# FIDO2AUTH_0022.net
KiCad netlist of a schematic drawn in EAGLE
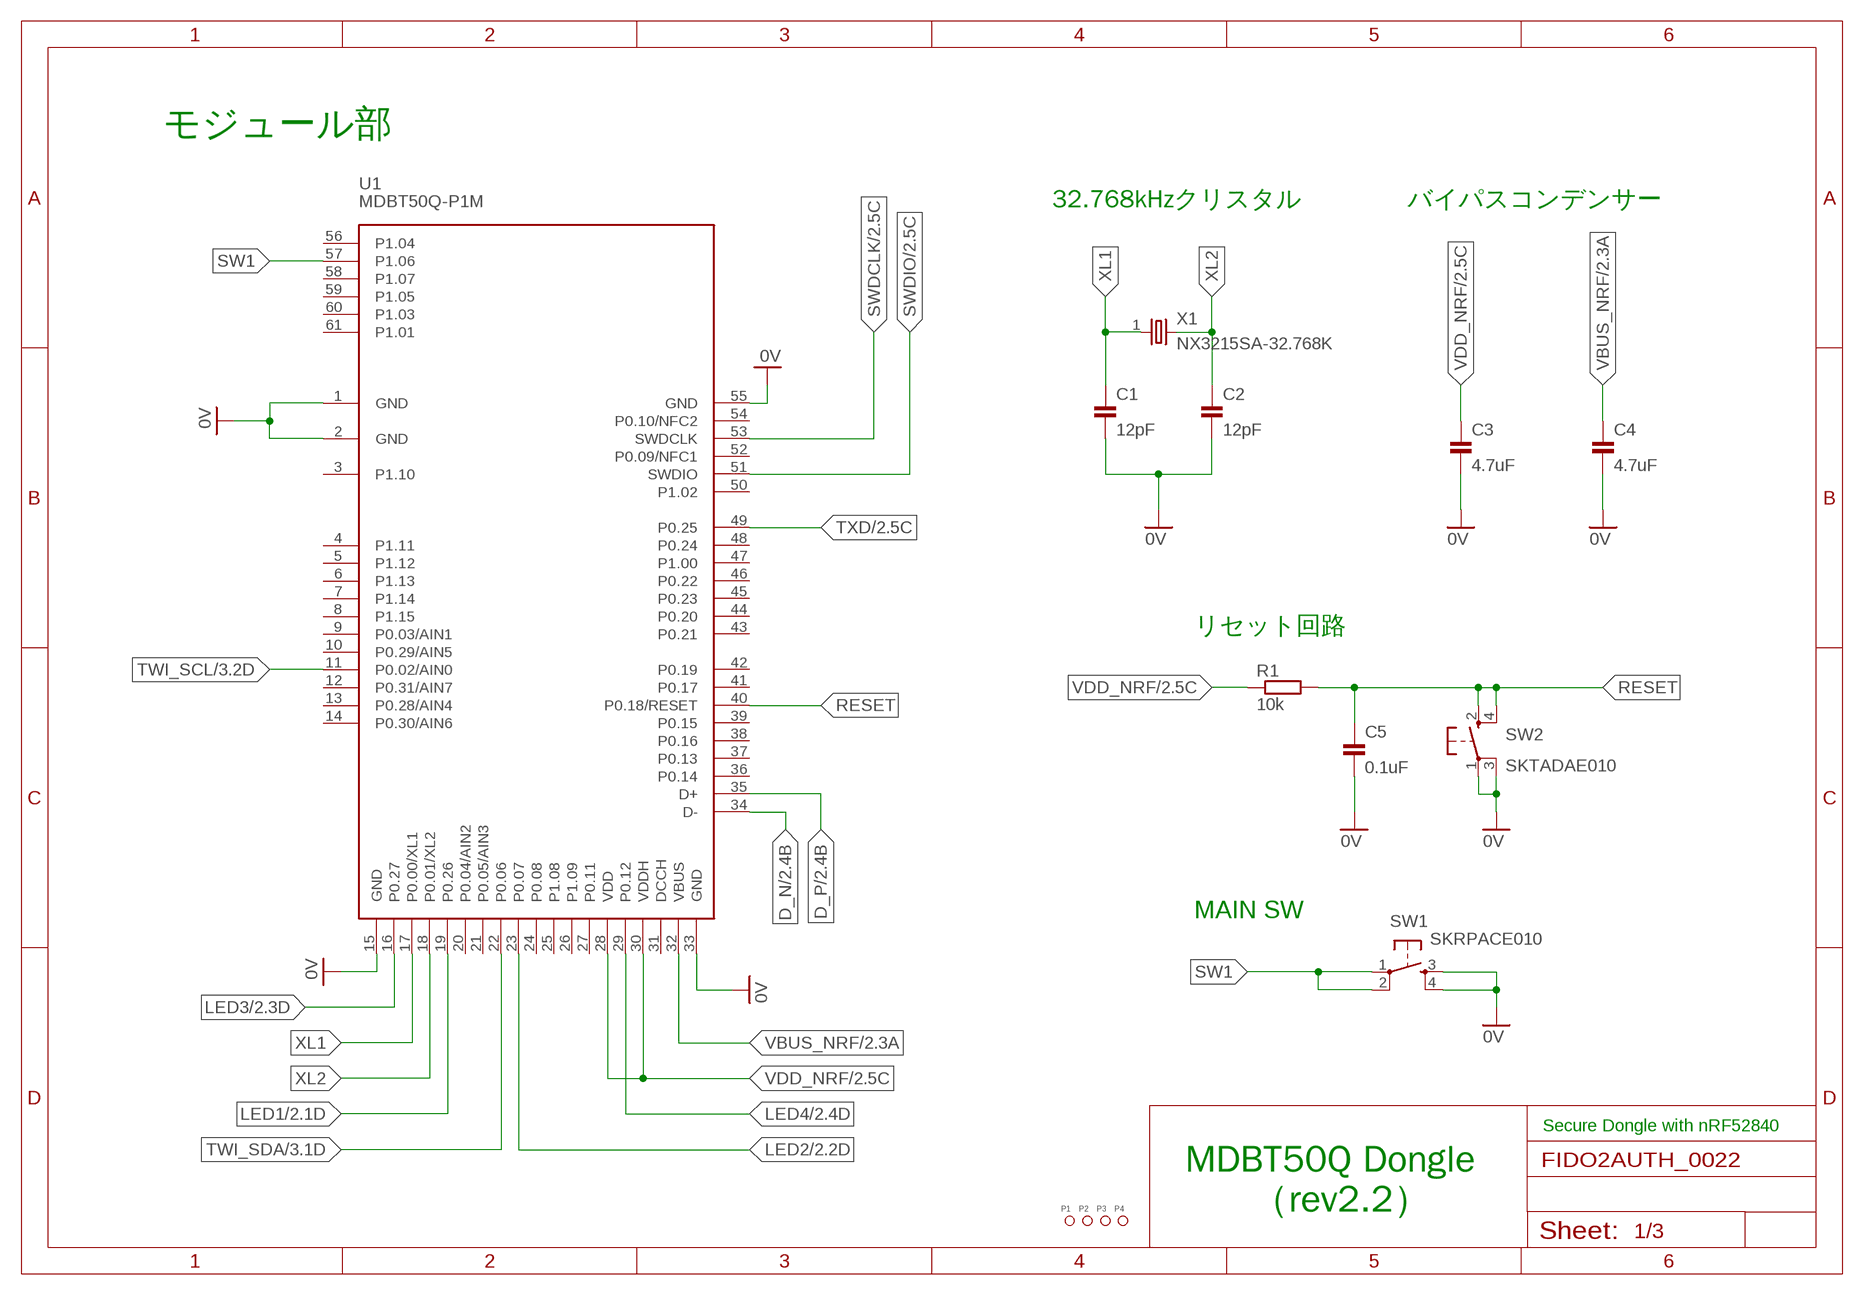
[diagram p0: schematic, sheet 1]
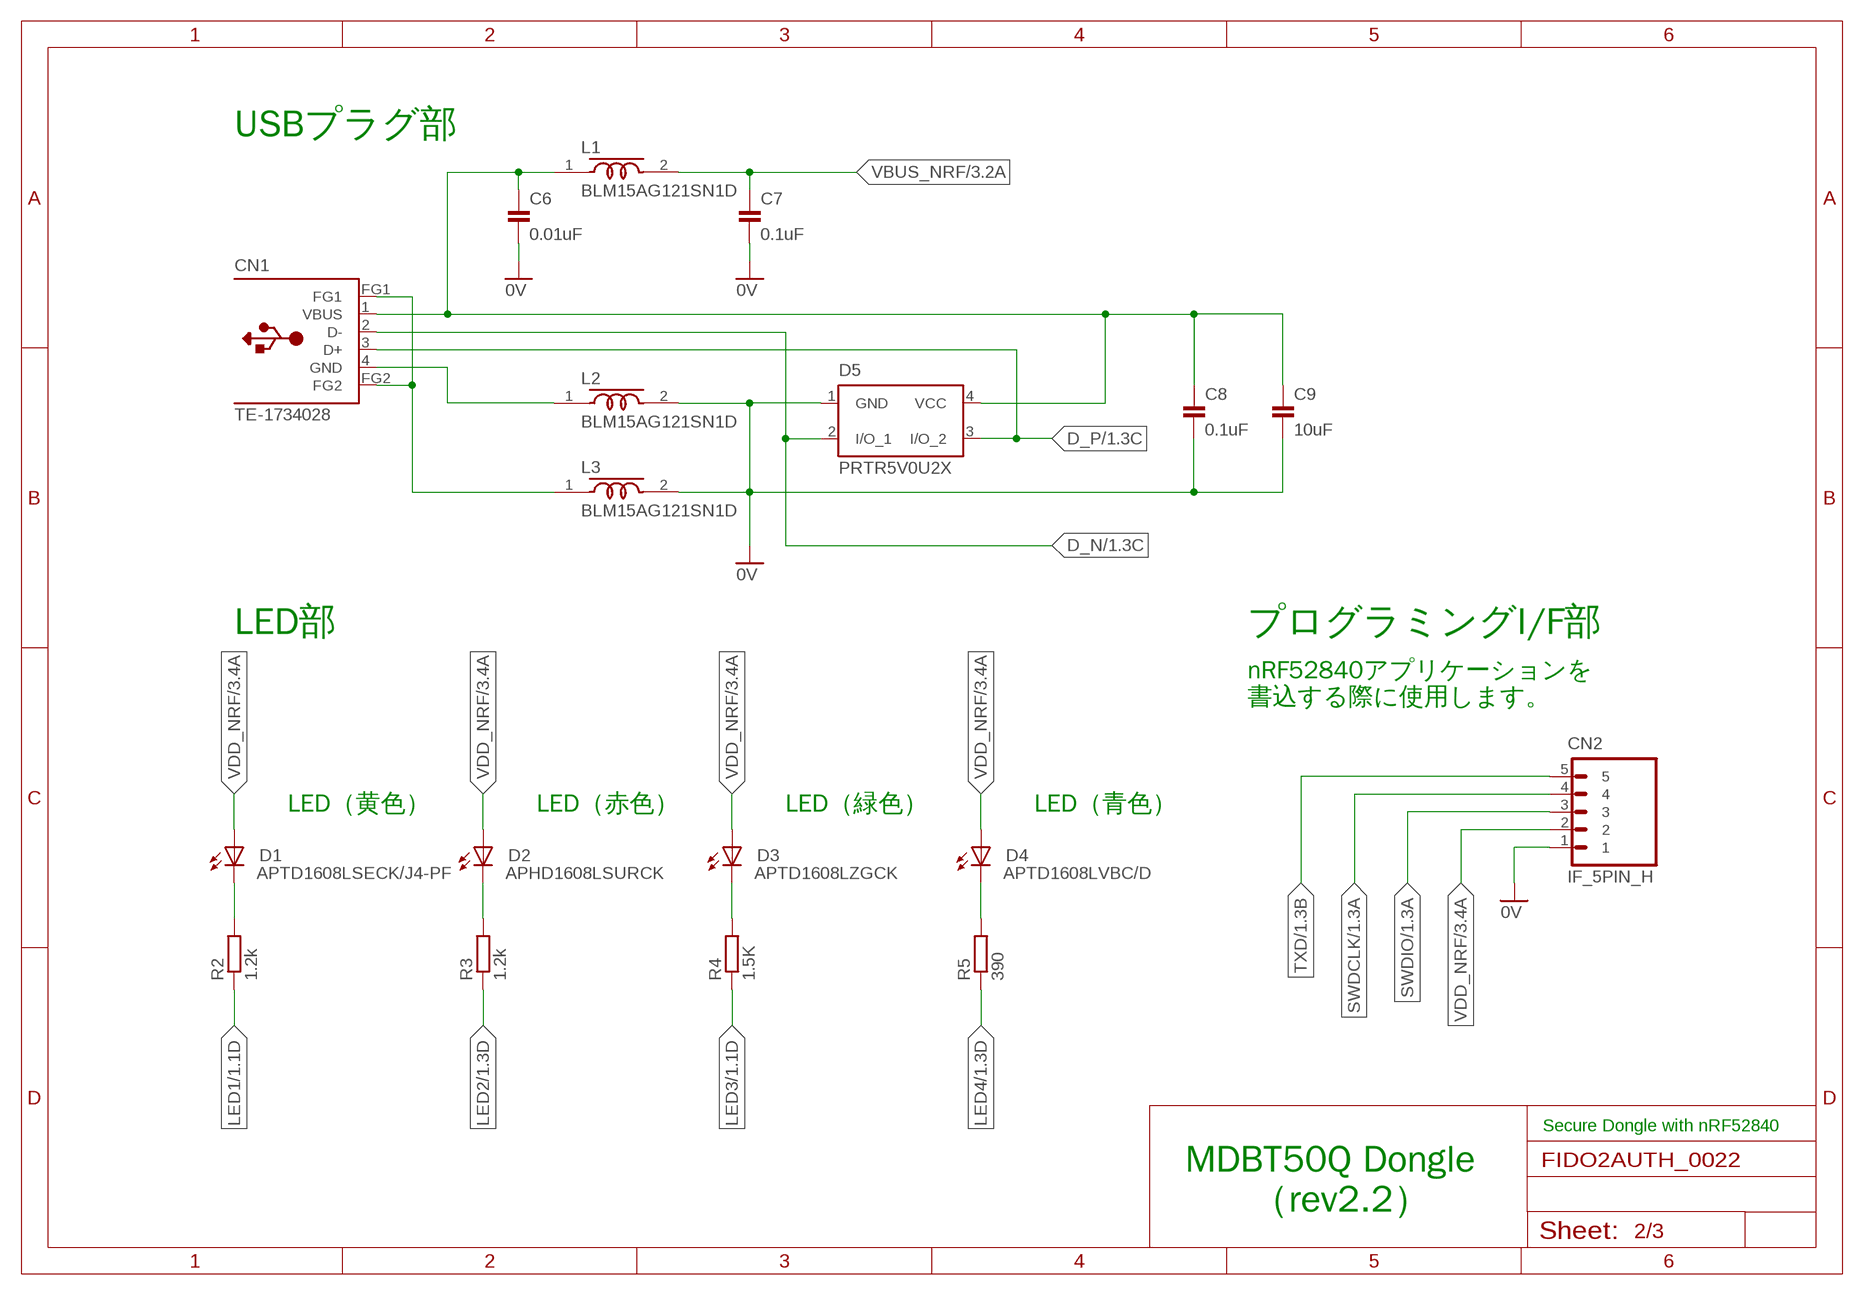
[diagram p1: schematic, sheet 2]
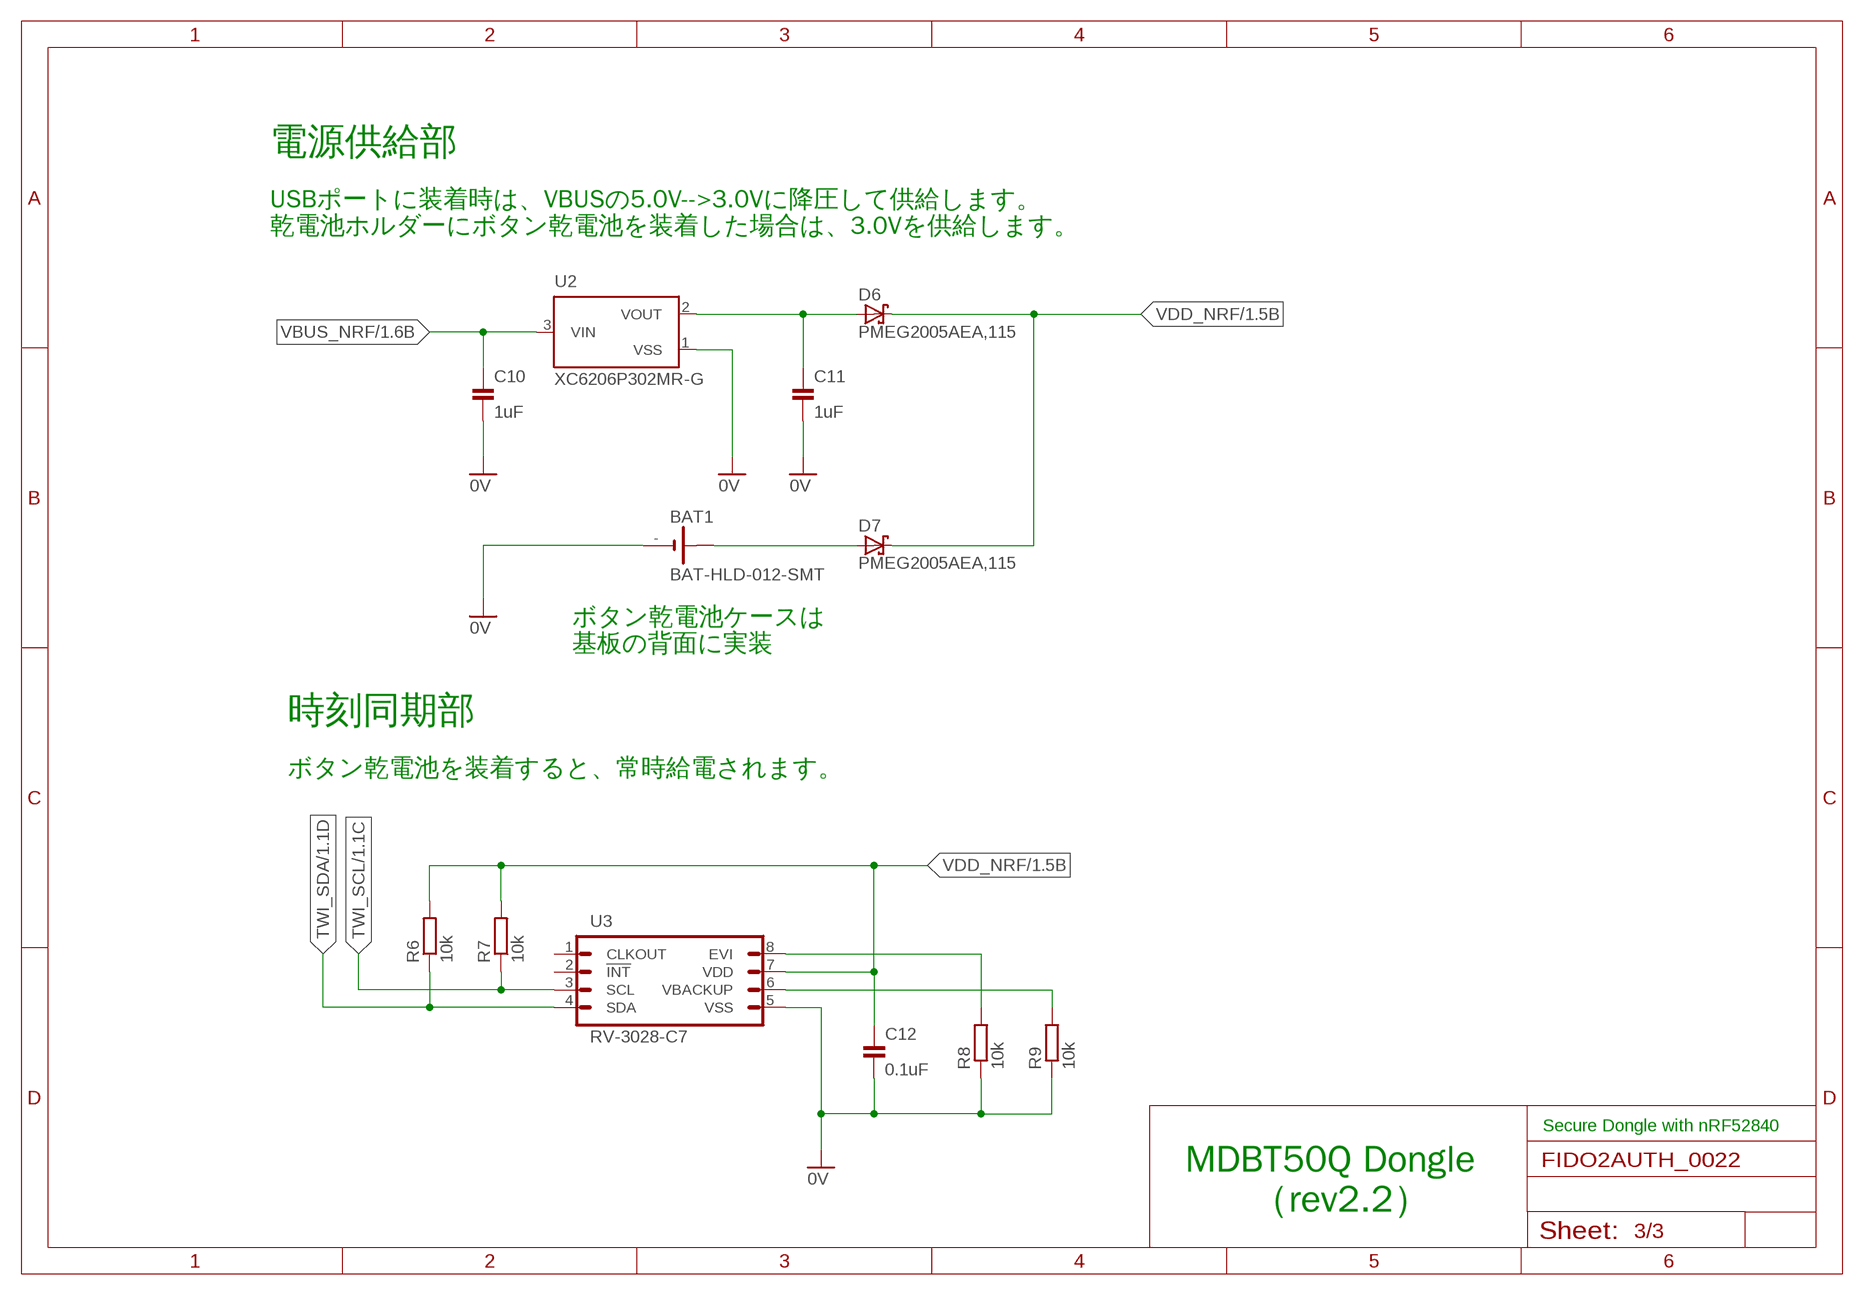
[diagram p2: schematic, sheet 3]

(export (version "E")
  (design (tool "Eeschema 10.0.6"))
  (components
    (comp (ref "C6")
      (value "0.01uF")
      (footprint "eagle-import:C0402N")
      (libsource (lib "eagle-import") (part "CAP_0402N"))
    )
    (comp (ref "C7")
      (value "0.1uF")
      (footprint "eagle-import:C0402N")
      (libsource (lib "eagle-import") (part "CAP_0402N"))
    )
    (comp (ref "C8")
      (value "0.1uF")
      (footprint "eagle-import:C0402N")
      (libsource (lib "eagle-import") (part "CAP_0402N"))
    )
    (comp (ref "C9")
      (value "10uF")
      (footprint "eagle-import:C0603N")
      (libsource (lib "eagle-import") (part "CAP_0603N"))
    )
    (comp (ref "CN1")
      (value "TE-1734028")
      (footprint "eagle-import:TE-1734028")
      (libsource (lib "eagle-import") (part "TE-1734028"))
    )
    (comp (ref "CN2")
      (value "IF_5PIN_H")
      (footprint "eagle-import:HEADER_5PIN")
      (libsource (lib "eagle-import") (part "IF_5PIN_H"))
    )
    (comp (ref "D1")
      (value "APTD1608LSECK/J4-PF")
      (footprint "eagle-import:APTD1608")
      (libsource (lib "eagle-import") (part "APTD1608LSECK/J4-PF"))
    )
    (comp (ref "D2")
      (value "APHD1608LSURCK")
      (footprint "eagle-import:APTD1608")
      (libsource (lib "eagle-import") (part "APHD1608LSURCK"))
    )
    (comp (ref "D3")
      (value "APTD1608LZGCK")
      (footprint "eagle-import:APTD1608")
      (libsource (lib "eagle-import") (part "APTD1608LZGCK"))
    )
    (comp (ref "D4")
      (value "APTD1608LVBC/D")
      (footprint "eagle-import:APTD1608")
      (libsource (lib "eagle-import") (part "APTD1608LVBC/D"))
    )
    (comp (ref "D5")
      (value "PRTR5V0U2X")
      (footprint "eagle-import:SOT143B")
      (libsource (lib "eagle-import") (part "PRTR5V0U2X"))
    )
    (comp (ref "L1")
      (value "BLM15AG121SN1D")
      (footprint "eagle-import:C0402N")
      (libsource (lib "eagle-import") (part "BLM15AG121SN1D"))
    )
    (comp (ref "L2")
      (value "BLM15AG121SN1D")
      (footprint "eagle-import:C0402N")
      (libsource (lib "eagle-import") (part "BLM15AG121SN1D"))
    )
    (comp (ref "L3")
      (value "BLM15AG121SN1D")
      (footprint "eagle-import:C0402N")
      (libsource (lib "eagle-import") (part "BLM15AG121SN1D"))
    )
    (comp (ref "R2")
      (value "1.2k")
      (footprint "eagle-import:R0402N")
      (libsource (lib "eagle-import") (part "RESISTOR_0402N"))
    )
    (comp (ref "R3")
      (value "1.2k")
      (footprint "eagle-import:R0402N")
      (libsource (lib "eagle-import") (part "RESISTOR_0402N"))
    )
    (comp (ref "R4")
      (value "1.5K")
      (footprint "eagle-import:R0402N")
      (libsource (lib "eagle-import") (part "RESISTOR_0402N"))
    )
    (comp (ref "R5")
      (value "390")
      (footprint "eagle-import:R0402N")
      (libsource (lib "eagle-import") (part "RESISTOR_0402N"))
    )
    (comp (ref "C1")
      (value "12pF")
      (footprint "eagle-import:C0603N")
      (libsource (lib "eagle-import") (part "CAP_0603N"))
    )
    (comp (ref "C2")
      (value "12pF")
      (footprint "eagle-import:C0603N")
      (libsource (lib "eagle-import") (part "CAP_0603N"))
    )
    (comp (ref "C3")
      (value "4.7uF")
      (footprint "eagle-import:C0603N")
      (libsource (lib "eagle-import") (part "CAP_0603N"))
    )
    (comp (ref "C4")
      (value "4.7uF")
      (footprint "eagle-import:C0603N")
      (libsource (lib "eagle-import") (part "CAP_0603N"))
    )
    (comp (ref "C5")
      (value "0.1uF")
      (footprint "eagle-import:C0402N")
      (libsource (lib "eagle-import") (part "CAP_0402N"))
    )
    (comp (ref "P1")
      (value "0")
      (footprint "eagle-import:ROUND-MARK-1.0")
      (fields (field (name "PARTNO") "DNP"))
      (libsource (lib "eagle-import") (part "PAD-MARK"))
    )
    (comp (ref "P2")
      (value "0")
      (footprint "eagle-import:ROUND-MARK-1.0")
      (fields (field (name "PARTNO") "DNP"))
      (libsource (lib "eagle-import") (part "PAD-MARK"))
    )
    (comp (ref "P3")
      (value "0")
      (footprint "eagle-import:ROUND-MARK-1.0")
      (fields (field (name "PARTNO") "DNP"))
      (libsource (lib "eagle-import") (part "PAD-MARK"))
    )
    (comp (ref "P4")
      (value "0")
      (footprint "eagle-import:ROUND-MARK-1.0")
      (fields (field (name "PARTNO") "DNP"))
      (libsource (lib "eagle-import") (part "PAD-MARK"))
    )
    (comp (ref "R1")
      (value "10k")
      (footprint "eagle-import:R0402N")
      (libsource (lib "eagle-import") (part "RESISTOR_0402N"))
    )
    (comp (ref "SW1")
      (value "SKRPACE010")
      (footprint "eagle-import:SKRPACE010")
      (libsource (lib "eagle-import") (part "SKRPACE010"))
    )
    (comp (ref "SW2")
      (value "SKTADAE010")
      (footprint "eagle-import:SKTADAE010")
      (libsource (lib "eagle-import") (part "SKTADAE010"))
    )
    (comp (ref "U1")
      (value "MDBT50Q-P1M")
      (footprint "eagle-import:MDBT50Q-P1M")
      (libsource (lib "eagle-import") (part "MDBT50Q-P1M"))
    )
    (comp (ref "X1")
      (value "NX3215SA-32.768K")
      (footprint "eagle-import:NX3215")
      (libsource (lib "eagle-import") (part "NX3215SA-32.768K"))
    )
    (comp (ref "BAT1")
      (value "BAT-HLD-012-SMT")
      (footprint "eagle-import:BAT-HLD-012-SMT")
      (libsource (lib "eagle-import") (part "BAT-HLD-012-SMT"))
    )
    (comp (ref "C10")
      (value "1uF")
      (footprint "eagle-import:C0603N")
      (libsource (lib "eagle-import") (part "CAP_0603N"))
    )
    (comp (ref "C11")
      (value "1uF")
      (footprint "eagle-import:C0603N")
      (libsource (lib "eagle-import") (part "CAP_0603N"))
    )
    (comp (ref "C12")
      (value "0.1uF")
      (footprint "eagle-import:C0402N")
      (libsource (lib "eagle-import") (part "CAP_0402N"))
    )
    (comp (ref "D6")
      (value "PMEG2005AEA,115")
      (footprint "eagle-import:SOD323-W")
      (libsource (lib "eagle-import") (part "PMEG2005AEA,115"))
    )
    (comp (ref "D7")
      (value "PMEG2005AEA,115")
      (footprint "eagle-import:SOD323-W")
      (libsource (lib "eagle-import") (part "PMEG2005AEA,115"))
    )
    (comp (ref "R6")
      (value "10k")
      (footprint "eagle-import:R0402N")
      (libsource (lib "eagle-import") (part "RESISTOR_0402N"))
    )
    (comp (ref "R7")
      (value "10k")
      (footprint "eagle-import:R0402N")
      (libsource (lib "eagle-import") (part "RESISTOR_0402N"))
    )
    (comp (ref "R8")
      (value "10k")
      (footprint "eagle-import:R0402N")
      (libsource (lib "eagle-import") (part "RESISTOR_0402N"))
    )
    (comp (ref "R9")
      (value "10k")
      (footprint "eagle-import:R0402N")
      (libsource (lib "eagle-import") (part "RESISTOR_0402N"))
    )
    (comp (ref "U2")
      (value "XC6206P302MR-G")
      (footprint "eagle-import:SOT23")
      (libsource (lib "eagle-import") (part "XC6206P302MR-G"))
    )
    (comp (ref "U3")
      (value "RV-3028-C7")
      (footprint "eagle-import:SON-8")
      (libsource (lib "eagle-import") (part "RV-3028-C7"))
    )
  )
  (nets
    (net (code "1") (name "0V") (class "Default")
      (node (ref "BAT1") (pin "-") (pinfunction "-_-") (pintype "passive"))
      (node (ref "C1") (pin "2") (pinfunction "2_2") (pintype "passive"))
      (node (ref "C10") (pin "2") (pinfunction "2_2") (pintype "passive"))
      (node (ref "C11") (pin "2") (pinfunction "2_2") (pintype "passive"))
      (node (ref "C12") (pin "2") (pinfunction "2_2") (pintype "passive"))
      (node (ref "C2") (pin "2") (pinfunction "2_2") (pintype "passive"))
      (node (ref "C3") (pin "2") (pinfunction "2_2") (pintype "passive"))
      (node (ref "C4") (pin "2") (pinfunction "2_2") (pintype "passive"))
      (node (ref "C5") (pin "2") (pinfunction "2_2") (pintype "passive"))
      (node (ref "C6") (pin "2") (pinfunction "2_2") (pintype "passive"))
      (node (ref "C7") (pin "2") (pinfunction "2_2") (pintype "passive"))
      (node (ref "C8") (pin "2") (pinfunction "2_2") (pintype "passive"))
      (node (ref "C9") (pin "2") (pinfunction "2_2") (pintype "passive"))
      (node (ref "CN2") (pin "1") (pinfunction "1_1") (pintype "passive"))
      (node (ref "D5") (pin "1") (pinfunction "GND_1") (pintype "passive"))
      (node (ref "L2") (pin "2") (pinfunction "2_2") (pintype "passive"))
      (node (ref "L3") (pin "2") (pinfunction "2_2") (pintype "passive"))
      (node (ref "R8") (pin "1") (pinfunction "1_1") (pintype "passive"))
      (node (ref "R9") (pin "1") (pinfunction "1_1") (pintype "passive"))
      (node (ref "SW1") (pin "3") (pinfunction "S_3") (pintype "passive"))
      (node (ref "SW1") (pin "4") (pinfunction "S1_4") (pintype "passive"))
      (node (ref "SW2") (pin "1") (pinfunction "P_1") (pintype "passive"))
      (node (ref "SW2") (pin "3") (pinfunction "P1_3") (pintype "passive"))
      (node (ref "U1") (pin "1") (pinfunction "GND_1") (pintype "bidirectional"))
      (node (ref "U1") (pin "15") (pinfunction "GND_15") (pintype "bidirectional"))
      (node (ref "U1") (pin "2") (pinfunction "GND_2") (pintype "bidirectional"))
      (node (ref "U1") (pin "33") (pinfunction "GND_33") (pintype "bidirectional"))
      (node (ref "U1") (pin "55") (pinfunction "GND_55") (pintype "bidirectional"))
      (node (ref "U2") (pin "1") (pinfunction "VSS_1") (pintype "passive"))
      (node (ref "U3") (pin "5") (pinfunction "VSS_5") (pintype "passive"))
    )
    (net (code "2") (name "D_N") (class "Default")
      (node (ref "CN1") (pin "2") (pinfunction "D-_2") (pintype "bidirectional"))
      (node (ref "D5") (pin "2") (pinfunction "I/O_1_2") (pintype "bidirectional"))
      (node (ref "U1") (pin "34") (pinfunction "D-_34") (pintype "bidirectional"))
    )
    (net (code "3") (name "D_P") (class "Default")
      (node (ref "CN1") (pin "3") (pinfunction "D+_3") (pintype "bidirectional"))
      (node (ref "D5") (pin "3") (pinfunction "I/O_2_3") (pintype "bidirectional"))
      (node (ref "U1") (pin "35") (pinfunction "D+_35") (pintype "bidirectional"))
    )
    (net (code "4") (name "LED1") (class "Default")
      (node (ref "R2") (pin "1") (pinfunction "1_1") (pintype "passive"))
      (node (ref "U1") (pin "19") (pinfunction "P0.26_19") (pintype "bidirectional"))
    )
    (net (code "5") (name "LED2") (class "Default")
      (node (ref "R3") (pin "1") (pinfunction "1_1") (pintype "passive"))
      (node (ref "U1") (pin "23") (pinfunction "P0.07_23") (pintype "bidirectional"))
    )
    (net (code "6") (name "LED3") (class "Default")
      (node (ref "R4") (pin "1") (pinfunction "1_1") (pintype "passive"))
      (node (ref "U1") (pin "16") (pinfunction "P0.27_16") (pintype "bidirectional"))
    )
    (net (code "7") (name "LED4") (class "Default")
      (node (ref "R5") (pin "1") (pinfunction "1_1") (pintype "passive"))
      (node (ref "U1") (pin "29") (pinfunction "P0.12_29") (pintype "bidirectional"))
    )
    (net (code "8") (name "Net-(BAT1-+)") (class "Default")
      (node (ref "BAT1") (pin "+@2") (pinfunction "+_+@2") (pintype "passive"))
      (node (ref "D7") (pin "A") (pinfunction "A_A") (pintype "passive"))
    )
    (net (code "9") (name "Net-(CN1-GND)") (class "Default")
      (node (ref "CN1") (pin "4") (pinfunction "GND_4") (pintype "passive"))
      (node (ref "L2") (pin "1") (pinfunction "1_1") (pintype "passive"))
    )
    (net (code "10") (name "Net-(CN1-PadFG1)") (class "Default")
      (node (ref "CN1") (pin "FG1") (pinfunction "FG1_FG1") (pintype "passive"))
      (node (ref "CN1") (pin "FG2") (pinfunction "FG2_FG2") (pintype "passive"))
      (node (ref "L3") (pin "1") (pinfunction "1_1") (pintype "passive"))
    )
    (net (code "11") (name "Net-(CN1-VBUS)") (class "Default")
      (node (ref "C6") (pin "1") (pinfunction "1_1") (pintype "passive"))
      (node (ref "C8") (pin "1") (pinfunction "1_1") (pintype "passive"))
      (node (ref "C9") (pin "1") (pinfunction "1_1") (pintype "passive"))
      (node (ref "CN1") (pin "1") (pinfunction "VBUS_1") (pintype "passive"))
      (node (ref "D5") (pin "4") (pinfunction "VCC_4") (pintype "passive"))
      (node (ref "L1") (pin "1") (pinfunction "1_1") (pintype "passive"))
    )
    (net (code "12") (name "Net-(D1-PadC)") (class "Default")
      (node (ref "D1") (pin "C") (pinfunction "C_C") (pintype "passive"))
      (node (ref "R2") (pin "2") (pinfunction "2_2") (pintype "passive"))
    )
    (net (code "13") (name "Net-(D2-PadC)") (class "Default")
      (node (ref "D2") (pin "C") (pinfunction "C_C") (pintype "passive"))
      (node (ref "R3") (pin "2") (pinfunction "2_2") (pintype "passive"))
    )
    (net (code "14") (name "Net-(D3-PadC)") (class "Default")
      (node (ref "D3") (pin "C") (pinfunction "C_C") (pintype "passive"))
      (node (ref "R4") (pin "2") (pinfunction "2_2") (pintype "passive"))
    )
    (net (code "15") (name "Net-(D4-PadC)") (class "Default")
      (node (ref "D4") (pin "C") (pinfunction "C_C") (pintype "passive"))
      (node (ref "R5") (pin "2") (pinfunction "2_2") (pintype "passive"))
    )
    (net (code "16") (name "Net-(U2-VOUT)") (class "Default")
      (node (ref "C11") (pin "1") (pinfunction "1_1") (pintype "passive"))
      (node (ref "D6") (pin "A") (pinfunction "A_A") (pintype "passive"))
      (node (ref "U2") (pin "2") (pinfunction "VOUT_2") (pintype "passive"))
    )
    (net (code "17") (name "Net-(U3-EVI)") (class "Default")
      (node (ref "R8") (pin "2") (pinfunction "2_2") (pintype "passive"))
      (node (ref "U3") (pin "8") (pinfunction "EVI_8") (pintype "bidirectional"))
    )
    (net (code "18") (name "Net-(U3-VBACKUP)") (class "Default")
      (node (ref "R9") (pin "2") (pinfunction "2_2") (pintype "passive"))
      (node (ref "U3") (pin "6") (pinfunction "VBACKUP_6") (pintype "passive"))
    )
    (net (code "19") (name "RESET") (class "Default")
      (node (ref "C5") (pin "1") (pinfunction "1_1") (pintype "passive"))
      (node (ref "R1") (pin "2") (pinfunction "2_2") (pintype "passive"))
      (node (ref "SW2") (pin "2") (pinfunction "S_2") (pintype "passive"))
      (node (ref "SW2") (pin "4") (pinfunction "S1_4") (pintype "passive"))
      (node (ref "U1") (pin "40") (pinfunction "P0.18/RESET_40") (pintype "bidirectional"))
    )
    (net (code "20") (name "SW1") (class "Default")
      (node (ref "SW1") (pin "1") (pinfunction "P_1") (pintype "passive"))
      (node (ref "SW1") (pin "2") (pinfunction "P1_2") (pintype "passive"))
      (node (ref "U1") (pin "57") (pinfunction "P1.06_57") (pintype "bidirectional"))
    )
    (net (code "21") (name "SWDCLK") (class "Default")
      (node (ref "CN2") (pin "4") (pinfunction "4_4") (pintype "passive"))
      (node (ref "U1") (pin "53") (pinfunction "SWDCLK_53") (pintype "bidirectional"))
    )
    (net (code "22") (name "SWDIO") (class "Default")
      (node (ref "CN2") (pin "3") (pinfunction "3_3") (pintype "passive"))
      (node (ref "U1") (pin "51") (pinfunction "SWDIO_51") (pintype "bidirectional"))
    )
    (net (code "23") (name "TWI_SCL") (class "Default")
      (node (ref "R7") (pin "1") (pinfunction "1_1") (pintype "passive"))
      (node (ref "U1") (pin "11") (pinfunction "P0.02/AIN0_11") (pintype "bidirectional"))
      (node (ref "U3") (pin "3") (pinfunction "SCL_3") (pintype "bidirectional"))
    )
    (net (code "24") (name "TWI_SDA") (class "Default")
      (node (ref "R6") (pin "1") (pinfunction "1_1") (pintype "passive"))
      (node (ref "U1") (pin "22") (pinfunction "P0.06_22") (pintype "bidirectional"))
      (node (ref "U3") (pin "4") (pinfunction "SDA_4") (pintype "bidirectional"))
    )
    (net (code "25") (name "TXD") (class "Default")
      (node (ref "CN2") (pin "5") (pinfunction "5_5") (pintype "passive"))
      (node (ref "U1") (pin "49") (pinfunction "P0.25_49") (pintype "bidirectional"))
    )
    (net (code "26") (name "VBUS_NRF") (class "Default")
      (node (ref "C10") (pin "1") (pinfunction "1_1") (pintype "passive"))
      (node (ref "C4") (pin "1") (pinfunction "1_1") (pintype "passive"))
      (node (ref "C7") (pin "1") (pinfunction "1_1") (pintype "passive"))
      (node (ref "L1") (pin "2") (pinfunction "2_2") (pintype "passive"))
      (node (ref "U1") (pin "32") (pinfunction "VBUS_32") (pintype "bidirectional"))
      (node (ref "U2") (pin "3") (pinfunction "VIN_3") (pintype "passive"))
    )
    (net (code "27") (name "VDD_NRF") (class "Default")
      (node (ref "C12") (pin "1") (pinfunction "1_1") (pintype "passive"))
      (node (ref "C3") (pin "1") (pinfunction "1_1") (pintype "passive"))
      (node (ref "CN2") (pin "2") (pinfunction "2_2") (pintype "passive"))
      (node (ref "D1") (pin "A") (pinfunction "A_A") (pintype "passive"))
      (node (ref "D2") (pin "A") (pinfunction "A_A") (pintype "passive"))
      (node (ref "D3") (pin "A") (pinfunction "A_A") (pintype "passive"))
      (node (ref "D4") (pin "A") (pinfunction "A_A") (pintype "passive"))
      (node (ref "D6") (pin "C") (pinfunction "C_C") (pintype "passive"))
      (node (ref "D7") (pin "C") (pinfunction "C_C") (pintype "passive"))
      (node (ref "R1") (pin "1") (pinfunction "1_1") (pintype "passive"))
      (node (ref "R6") (pin "2") (pinfunction "2_2") (pintype "passive"))
      (node (ref "R7") (pin "2") (pinfunction "2_2") (pintype "passive"))
      (node (ref "U1") (pin "28") (pinfunction "VDD_28") (pintype "bidirectional"))
      (node (ref "U1") (pin "30") (pinfunction "VDDH_30") (pintype "bidirectional"))
      (node (ref "U3") (pin "7") (pinfunction "VDD_7") (pintype "passive"))
    )
    (net (code "28") (name "XL1") (class "Default")
      (node (ref "C1") (pin "1") (pinfunction "1_1") (pintype "passive"))
      (node (ref "U1") (pin "17") (pinfunction "P0.00/XL1_17") (pintype "bidirectional"))
      (node (ref "X1") (pin "1") (pinfunction "1_1") (pintype "passive"))
    )
    (net (code "29") (name "XL2") (class "Default")
      (node (ref "C2") (pin "1") (pinfunction "1_1") (pintype "passive"))
      (node (ref "U1") (pin "18") (pinfunction "P0.01/XL2_18") (pintype "bidirectional"))
      (node (ref "X1") (pin "2") (pinfunction "2_2") (pintype "passive"))
    )
    (net (code "30") (name "unconnected-(U1-DCCH-Pad31)") (class "Default")
      (node (ref "U1") (pin "31") (pinfunction "DCCH_31") (pintype "bidirectional"))
    )
    (net (code "31") (name "unconnected-(U1-P0.03{slash}AIN1-Pad9)") (class "Default")
      (node (ref "U1") (pin "9") (pinfunction "P0.03/AIN1_9") (pintype "bidirectional"))
    )
    (net (code "32") (name "unconnected-(U1-P0.04{slash}AIN2-Pad20)") (class "Default")
      (node (ref "U1") (pin "20") (pinfunction "P0.04/AIN2_20") (pintype "bidirectional"))
    )
    (net (code "33") (name "unconnected-(U1-P0.05{slash}AIN3-Pad21)") (class "Default")
      (node (ref "U1") (pin "21") (pinfunction "P0.05/AIN3_21") (pintype "bidirectional"))
    )
    (net (code "34") (name "unconnected-(U1-P0.08-Pad24)") (class "Default")
      (node (ref "U1") (pin "24") (pinfunction "P0.08_24") (pintype "bidirectional"))
    )
    (net (code "35") (name "unconnected-(U1-P0.09{slash}NFC1-Pad52)") (class "Default")
      (node (ref "U1") (pin "52") (pinfunction "P0.09/NFC1_52") (pintype "bidirectional"))
    )
    (net (code "36") (name "unconnected-(U1-P0.10{slash}NFC2-Pad54)") (class "Default")
      (node (ref "U1") (pin "54") (pinfunction "P0.10/NFC2_54") (pintype "bidirectional"))
    )
    (net (code "37") (name "unconnected-(U1-P0.11-Pad27)") (class "Default")
      (node (ref "U1") (pin "27") (pinfunction "P0.11_27") (pintype "bidirectional"))
    )
    (net (code "38") (name "unconnected-(U1-P0.13-Pad37)") (class "Default")
      (node (ref "U1") (pin "37") (pinfunction "P0.13_37") (pintype "bidirectional"))
    )
    (net (code "39") (name "unconnected-(U1-P0.14-Pad36)") (class "Default")
      (node (ref "U1") (pin "36") (pinfunction "P0.14_36") (pintype "bidirectional"))
    )
    (net (code "40") (name "unconnected-(U1-P0.15-Pad39)") (class "Default")
      (node (ref "U1") (pin "39") (pinfunction "P0.15_39") (pintype "bidirectional"))
    )
    (net (code "41") (name "unconnected-(U1-P0.16-Pad38)") (class "Default")
      (node (ref "U1") (pin "38") (pinfunction "P0.16_38") (pintype "bidirectional"))
    )
    (net (code "42") (name "unconnected-(U1-P0.17-Pad41)") (class "Default")
      (node (ref "U1") (pin "41") (pinfunction "P0.17_41") (pintype "bidirectional"))
    )
    (net (code "43") (name "unconnected-(U1-P0.19-Pad42)") (class "Default")
      (node (ref "U1") (pin "42") (pinfunction "P0.19_42") (pintype "bidirectional"))
    )
    (net (code "44") (name "unconnected-(U1-P0.20-Pad44)") (class "Default")
      (node (ref "U1") (pin "44") (pinfunction "P0.20_44") (pintype "bidirectional"))
    )
    (net (code "45") (name "unconnected-(U1-P0.21-Pad43)") (class "Default")
      (node (ref "U1") (pin "43") (pinfunction "P0.21_43") (pintype "bidirectional"))
    )
    (net (code "46") (name "unconnected-(U1-P0.22-Pad46)") (class "Default")
      (node (ref "U1") (pin "46") (pinfunction "P0.22_46") (pintype "bidirectional"))
    )
    (net (code "47") (name "unconnected-(U1-P0.23-Pad45)") (class "Default")
      (node (ref "U1") (pin "45") (pinfunction "P0.23_45") (pintype "bidirectional"))
    )
    (net (code "48") (name "unconnected-(U1-P0.24-Pad48)") (class "Default")
      (node (ref "U1") (pin "48") (pinfunction "P0.24_48") (pintype "bidirectional"))
    )
    (net (code "49") (name "unconnected-(U1-P0.28{slash}AIN4-Pad13)") (class "Default")
      (node (ref "U1") (pin "13") (pinfunction "P0.28/AIN4_13") (pintype "bidirectional"))
    )
    (net (code "50") (name "unconnected-(U1-P0.29{slash}AIN5-Pad10)") (class "Default")
      (node (ref "U1") (pin "10") (pinfunction "P0.29/AIN5_10") (pintype "bidirectional"))
    )
    (net (code "51") (name "unconnected-(U1-P0.30{slash}AIN6-Pad14)") (class "Default")
      (node (ref "U1") (pin "14") (pinfunction "P0.30/AIN6_14") (pintype "bidirectional"))
    )
    (net (code "52") (name "unconnected-(U1-P0.31{slash}AIN7-Pad12)") (class "Default")
      (node (ref "U1") (pin "12") (pinfunction "P0.31/AIN7_12") (pintype "bidirectional"))
    )
    (net (code "53") (name "unconnected-(U1-P1.00-Pad47)") (class "Default")
      (node (ref "U1") (pin "47") (pinfunction "P1.00_47") (pintype "bidirectional"))
    )
    (net (code "54") (name "unconnected-(U1-P1.01-Pad61)") (class "Default")
      (node (ref "U1") (pin "61") (pinfunction "P1.01_61") (pintype "bidirectional"))
    )
    (net (code "55") (name "unconnected-(U1-P1.02-Pad50)") (class "Default")
      (node (ref "U1") (pin "50") (pinfunction "P1.02_50") (pintype "bidirectional"))
    )
    (net (code "56") (name "unconnected-(U1-P1.03-Pad60)") (class "Default")
      (node (ref "U1") (pin "60") (pinfunction "P1.03_60") (pintype "bidirectional"))
    )
    (net (code "57") (name "unconnected-(U1-P1.04-Pad56)") (class "Default")
      (node (ref "U1") (pin "56") (pinfunction "P1.04_56") (pintype "bidirectional"))
    )
    (net (code "58") (name "unconnected-(U1-P1.05-Pad59)") (class "Default")
      (node (ref "U1") (pin "59") (pinfunction "P1.05_59") (pintype "bidirectional"))
    )
    (net (code "59") (name "unconnected-(U1-P1.07-Pad58)") (class "Default")
      (node (ref "U1") (pin "58") (pinfunction "P1.07_58") (pintype "bidirectional"))
    )
    (net (code "60") (name "unconnected-(U1-P1.08-Pad25)") (class "Default")
      (node (ref "U1") (pin "25") (pinfunction "P1.08_25") (pintype "bidirectional"))
    )
    (net (code "61") (name "unconnected-(U1-P1.09-Pad26)") (class "Default")
      (node (ref "U1") (pin "26") (pinfunction "P1.09_26") (pintype "bidirectional"))
    )
    (net (code "62") (name "unconnected-(U1-P1.10-Pad3)") (class "Default")
      (node (ref "U1") (pin "3") (pinfunction "P1.10_3") (pintype "bidirectional"))
    )
    (net (code "63") (name "unconnected-(U1-P1.11-Pad4)") (class "Default")
      (node (ref "U1") (pin "4") (pinfunction "P1.11_4") (pintype "bidirectional"))
    )
    (net (code "64") (name "unconnected-(U1-P1.12-Pad5)") (class "Default")
      (node (ref "U1") (pin "5") (pinfunction "P1.12_5") (pintype "bidirectional"))
    )
    (net (code "65") (name "unconnected-(U1-P1.13-Pad6)") (class "Default")
      (node (ref "U1") (pin "6") (pinfunction "P1.13_6") (pintype "bidirectional"))
    )
    (net (code "66") (name "unconnected-(U1-P1.14-Pad7)") (class "Default")
      (node (ref "U1") (pin "7") (pinfunction "P1.14_7") (pintype "bidirectional"))
    )
    (net (code "67") (name "unconnected-(U1-P1.15-Pad8)") (class "Default")
      (node (ref "U1") (pin "8") (pinfunction "P1.15_8") (pintype "bidirectional"))
    )
    (net (code "68") (name "unconnected-(U3-CLKOUT-Pad1)") (class "Default")
      (node (ref "U3") (pin "1") (pinfunction "CLKOUT_1") (pintype "bidirectional"))
    )
    (net (code "69") (name "unconnected-(U3-~{INT}-Pad2)") (class "Default")
      (node (ref "U3") (pin "2") (pinfunction "~{INT}_2") (pintype "bidirectional"))
    )
  )
)
